# Sheet1.net
KiCad netlist of a schematic drawn in Altium Designer
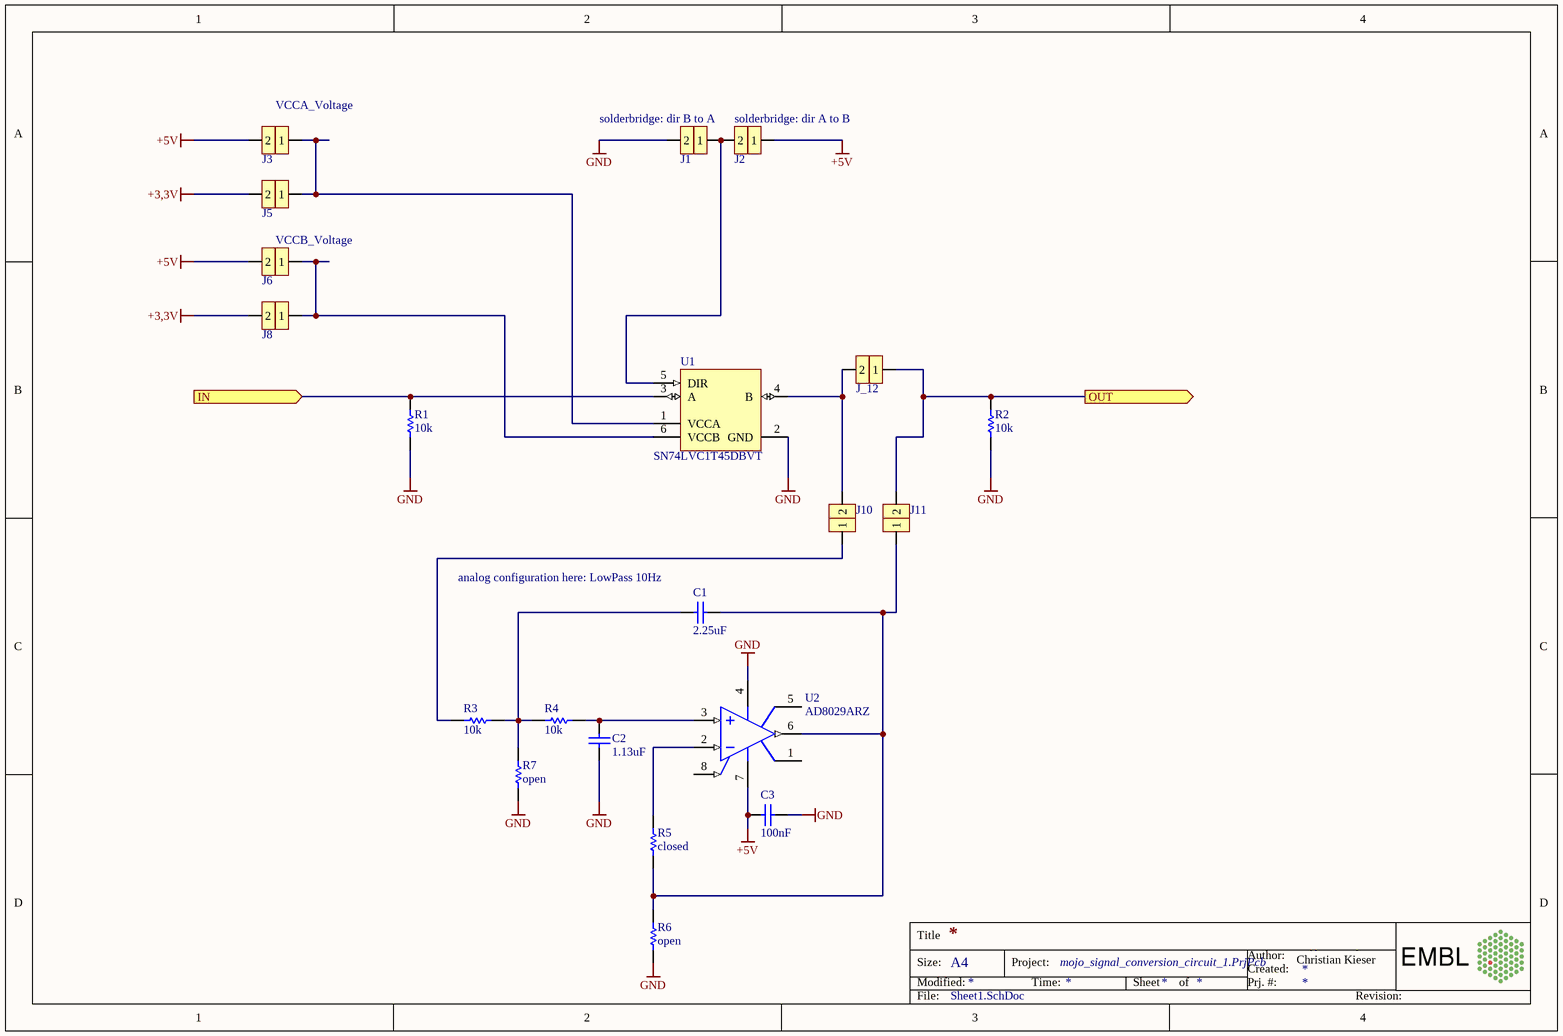
[diagram p0: Sheet1.SchDoc]

(export (version "E")
  (design (tool "Eeschema 10.0.6"))
  (components
    (comp (ref "C1")
      (value "2.25uF")
      (footprint "CAPC1206(3216)190_N")
      (description "CAP CER 1UF 10V X7R 1206")
      (fields
        (field (name "MANUFACTURER") "Wurth Electronics Inc.")
        (field (name "MANUFACTURER PART NUMBER") "885012208013")
      )
      (libsource (lib "Altium Vault EMBL 3") (part "CMP-001-0138-A.1"))
    )
    (comp (ref "C2")
      (value "1.13uF")
      (footprint "CAPC1206(3216)190_N")
      (description "CAP CER 1UF 10V X7R 1206")
      (fields
        (field (name "MANUFACTURER") "Wurth Electronics Inc.")
        (field (name "MANUFACTURER PART NUMBER") "885012208013")
      )
      (libsource (lib "Altium Vault EMBL 3") (part "CMP-001-0138-A.1"))
    )
    (comp (ref "C3")
      (value "100nF")
      (footprint "CAPC2013X88X50ML20T25")
      (description "generic 0805 COG oder X7R Vielschichtkondensatoren max. +/-10%")
      (libsource (lib "Altium Vault EMBL") (part "CMP-001-0082-2"))
    )
    (comp (ref "J1")
      (value "normal solderbridge")
      (footprint "PCBComponent")
      (libsource (lib "Altium Vault EMBL") (part "CMP-001-0133-A.1"))
    )
    (comp (ref "J2")
      (value "normal solderbridge")
      (footprint "PCBComponent")
      (libsource (lib "Altium Vault EMBL") (part "CMP-001-0133-A.1"))
    )
    (comp (ref "J3")
      (value "normal solderbridge")
      (footprint "PCBComponent")
      (libsource (lib "Altium Vault EMBL") (part "CMP-001-0133-A.1"))
    )
    (comp (ref "J5")
      (value "normal solderbridge")
      (footprint "PCBComponent")
      (libsource (lib "Altium Vault EMBL") (part "CMP-001-0133-A.1"))
    )
    (comp (ref "J6")
      (value "normal solderbridge")
      (footprint "PCBComponent")
      (libsource (lib "Altium Vault EMBL") (part "CMP-001-0133-A.1"))
    )
    (comp (ref "J8")
      (value "normal solderbridge")
      (footprint "PCBComponent")
      (libsource (lib "Altium Vault EMBL") (part "CMP-001-0133-A.1"))
    )
    (comp (ref "J10")
      (value "normal solderbridge")
      (footprint "PCBComponent")
      (libsource (lib "") (part "CMP-001-0133-A.1_1"))
    )
    (comp (ref "J11")
      (value "normal solderbridge")
      (footprint "PCBComponent")
      (libsource (lib "") (part "CMP-001-0133-A.1_1"))
    )
    (comp (ref "J_12")
      (value "normal solderbridge")
      (footprint "PCBComponent")
      (libsource (lib "Altium Vault EMBL") (part "CMP-001-0133-A.1"))
    )
    (comp (ref "R1")
      (value "10k")
      (footprint "YAGO-RC0805_M")
      (description "0805 Yageo Standard BlackBox Resistors")
      (fields (field (name "TOLERANCE") "±1%") (field (name "MANUFACTURER") "Yageo"))
      (libsource (lib "Altium Vault EMBL") (part "CMP-001-0027-2"))
    )
    (comp (ref "R2")
      (value "10k")
      (footprint "YAGO-RC0805_M")
      (description "0805 Yageo Standard BlackBox Resistors")
      (fields (field (name "TOLERANCE") "±1%") (field (name "MANUFACTURER") "Yageo"))
      (libsource (lib "Altium Vault EMBL") (part "CMP-001-0027-2"))
    )
    (comp (ref "R3")
      (value "10k")
      (footprint "YAGO-RC0805_M")
      (description "0805 Yageo Standard BlackBox Resistors")
      (fields (field (name "TOLERANCE") "±1%") (field (name "MANUFACTURER") "Yageo"))
      (libsource (lib "Altium Vault EMBL") (part "CMP-001-0027-2"))
    )
    (comp (ref "R4")
      (value "10k")
      (footprint "YAGO-RC0805_M")
      (description "0805 Yageo Standard BlackBox Resistors")
      (fields (field (name "TOLERANCE") "±1%") (field (name "MANUFACTURER") "Yageo"))
      (libsource (lib "Altium Vault EMBL") (part "CMP-001-0027-2"))
    )
    (comp (ref "R5")
      (value "closed")
      (footprint "YAGO-RC0805_M")
      (description "0805 Yageo Standard BlackBox Resistors")
      (fields (field (name "TOLERANCE") "±1%") (field (name "MANUFACTURER") "Yageo"))
      (libsource (lib "Altium Vault EMBL") (part "CMP-001-0027-2"))
    )
    (comp (ref "R6")
      (value "open")
      (footprint "YAGO-RC0805_M")
      (description "0805 Yageo Standard BlackBox Resistors")
      (fields (field (name "TOLERANCE") "±1%") (field (name "MANUFACTURER") "Yageo"))
      (libsource (lib "Altium Vault EMBL") (part "CMP-001-0027-2"))
    )
    (comp (ref "R7")
      (value "open")
      (footprint "YAGO-RC0805_M")
      (description "0805 Yageo Standard BlackBox Resistors")
      (fields (field (name "TOLERANCE") "±1%") (field (name "MANUFACTURER") "Yageo"))
      (libsource (lib "Altium Vault EMBL") (part "CMP-001-0027-2"))
    )
    (comp (ref "U1")
      (value "SN74LVC1T45DBVT")
      (footprint "DBV0006A_M")
      (fields
        (field (name "MANUFACTURER") "Texas Instruments")
        (field (name "GENERIC PART NUMBER") "SN74LVC1T45")
      )
      (libsource (lib "Altium Vault EMBL") (part "CMP-00492-1"))
    )
    (comp (ref "U2")
      (value "AD8029ARZ")
      (footprint "ADI-R-8_L")
      (fields (field (name "MANUFACTURER") "Analog Devices") (field (name "GENERIC PART NUMBER") "AD8029"))
      (libsource (lib "Altium Vault EMBL") (part "CMP-00480-1"))
    )
  )
  (nets
    (net (code "1") (name "+3,3V") (class "Default")
      (node (ref "J5") (pin "2") (pinfunction "2_2") (pintype "passive"))
      (node (ref "J8") (pin "2") (pinfunction "2_2") (pintype "passive"))
    )
    (net (code "2") (name "+5V") (class "Default")
      (node (ref "C3") (pin "2") (pinfunction "2_2") (pintype "passive"))
      (node (ref "J2") (pin "1") (pinfunction "1_1") (pintype "passive"))
      (node (ref "J3") (pin "2") (pinfunction "2_2") (pintype "passive"))
      (node (ref "J6") (pin "2") (pinfunction "2_2") (pintype "passive"))
      (node (ref "U2") (pin "7") (pinfunction "+VS_7") (pintype "power_in"))
    )
    (net (code "3") (name "/IN") (class "Default")
      (node (ref "R1") (pin "2") (pinfunction "2_2") (pintype "passive"))
      (node (ref "U1") (pin "3") (pinfunction "A_3") (pintype "bidirectional"))
    )
    (net (code "4") (name "/OUT") (class "Default")
      (node (ref "J11") (pin "2") (pinfunction "2_2") (pintype "passive"))
      (node (ref "J_12") (pin "1") (pinfunction "1_1") (pintype "passive"))
      (node (ref "R2") (pin "2") (pinfunction "2_2") (pintype "passive"))
    )
    (net (code "5") (name "GND") (class "Default")
      (node (ref "C2") (pin "1") (pinfunction "1_1") (pintype "passive"))
      (node (ref "C3") (pin "1") (pinfunction "1_1") (pintype "passive"))
      (node (ref "J1") (pin "2") (pinfunction "2_2") (pintype "passive"))
      (node (ref "R1") (pin "1") (pinfunction "1_1") (pintype "passive"))
      (node (ref "R2") (pin "1") (pinfunction "1_1") (pintype "passive"))
      (node (ref "R6") (pin "2") (pinfunction "2_2") (pintype "passive"))
      (node (ref "R7") (pin "2") (pinfunction "2_2") (pintype "passive"))
      (node (ref "U1") (pin "2") (pinfunction "GND_2") (pintype "power_in"))
      (node (ref "U2") (pin "4") (pinfunction "-VS_4") (pintype "power_in"))
    )
    (net (code "6") (name "Net-(C1-Pad1)") (class "Default")
      (node (ref "C1") (pin "1") (pinfunction "1_1") (pintype "passive"))
      (node (ref "R3") (pin "1") (pinfunction "1_1") (pintype "passive"))
      (node (ref "R4") (pin "2") (pinfunction "2_2") (pintype "passive"))
      (node (ref "R7") (pin "1") (pinfunction "1_1") (pintype "passive"))
    )
    (net (code "7") (name "Net-(J10-Pad1)") (class "Default")
      (node (ref "J10") (pin "1") (pinfunction "1_1") (pintype "passive"))
      (node (ref "R3") (pin "2") (pinfunction "2_2") (pintype "passive"))
    )
    (net (code "8") (name "Net-(U1-B)") (class "Default")
      (node (ref "J10") (pin "2") (pinfunction "2_2") (pintype "passive"))
      (node (ref "J_12") (pin "2") (pinfunction "2_2") (pintype "passive"))
      (node (ref "U1") (pin "4") (pinfunction "B_4") (pintype "bidirectional"))
    )
    (net (code "9") (name "Net-(U1-DIR)") (class "Default")
      (node (ref "J1") (pin "1") (pinfunction "1_1") (pintype "passive"))
      (node (ref "J2") (pin "2") (pinfunction "2_2") (pintype "passive"))
      (node (ref "U1") (pin "5") (pinfunction "DIR_5") (pintype "input"))
    )
    (net (code "10") (name "Net-(U1-VCCA)") (class "Default")
      (node (ref "J3") (pin "1") (pinfunction "1_1") (pintype "passive"))
      (node (ref "J5") (pin "1") (pinfunction "1_1") (pintype "passive"))
      (node (ref "U1") (pin "1") (pinfunction "VCCA_1") (pintype "power_in"))
    )
    (net (code "11") (name "Net-(U1-VCCB)") (class "Default")
      (node (ref "J6") (pin "1") (pinfunction "1_1") (pintype "passive"))
      (node (ref "J8") (pin "1") (pinfunction "1_1") (pintype "passive"))
      (node (ref "U1") (pin "6") (pinfunction "VCCB_6") (pintype "power_in"))
    )
    (net (code "12") (name "Net-(U2-+IN)") (class "Default")
      (node (ref "C2") (pin "2") (pinfunction "2_2") (pintype "passive"))
      (node (ref "R4") (pin "1") (pinfunction "1_1") (pintype "passive"))
      (node (ref "U2") (pin "3") (pinfunction "+IN_3") (pintype "input"))
    )
    (net (code "13") (name "Net-(U2--IN)") (class "Default")
      (node (ref "R5") (pin "1") (pinfunction "1_1") (pintype "passive"))
      (node (ref "U2") (pin "2") (pinfunction "-IN_2") (pintype "input"))
    )
    (net (code "14") (name "Net-(U2-VOUT)") (class "Default")
      (node (ref "C1") (pin "2") (pinfunction "2_2") (pintype "passive"))
      (node (ref "J11") (pin "1") (pinfunction "1_1") (pintype "passive"))
      (node (ref "R5") (pin "2") (pinfunction "2_2") (pintype "passive"))
      (node (ref "R6") (pin "1") (pinfunction "1_1") (pintype "passive"))
      (node (ref "U2") (pin "6") (pinfunction "VOUT_6") (pintype "output"))
    )
    (net (code "15") (name "unconnected-(U2-NC-Pad1)") (class "Default")
      (node (ref "U2") (pin "1") (pinfunction "NC_1") (pintype "passive"))
    )
    (net (code "16") (name "unconnected-(U2-NC-Pad5)") (class "Default")
      (node (ref "U2") (pin "5") (pinfunction "NC_5") (pintype "passive"))
    )
    (net (code "17") (name "unconnected-(U2-~{DISABLE}-Pad8)") (class "Default")
      (node (ref "U2") (pin "8") (pinfunction "~{DISABLE}_8") (pintype "input"))
    )
  )
)
